# Motor-Z.net
KiCad netlist of a schematic drawn in Altium Designer
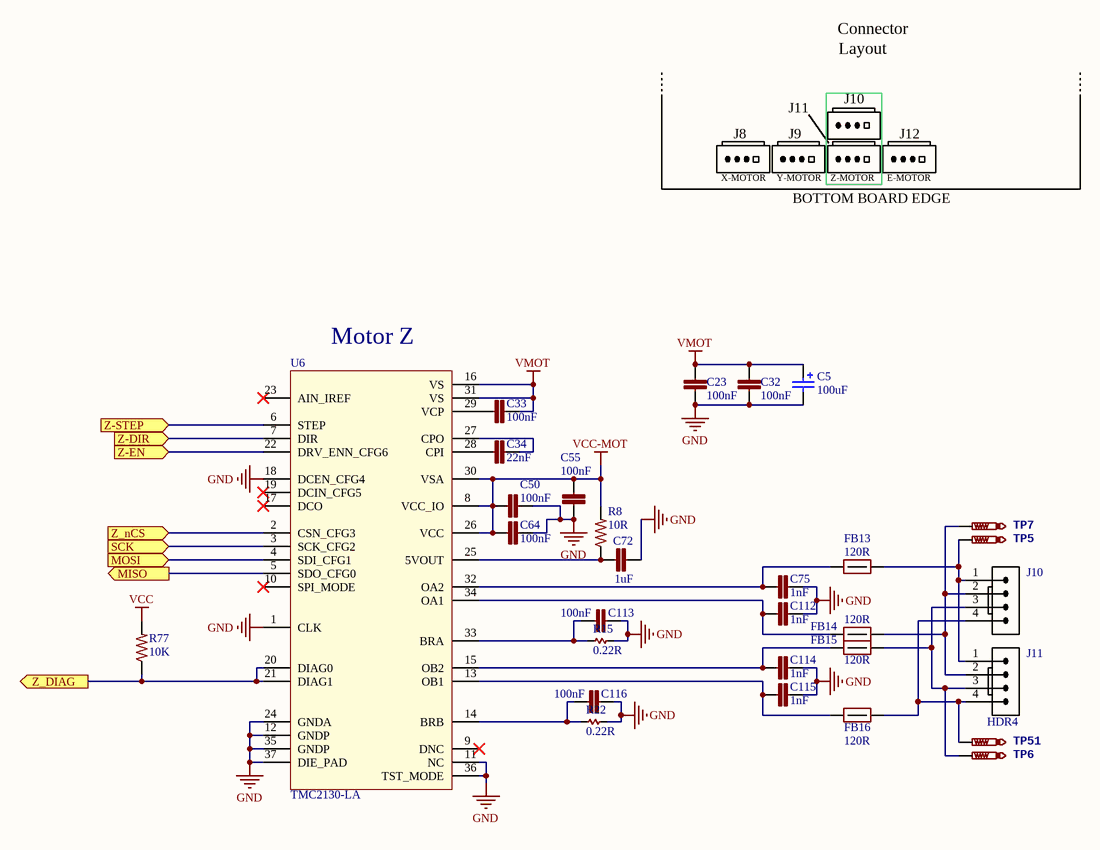
[diagram p0: Motor-Z.SchDoc]

(export (version "E")
  (design (tool "Eeschema 10.0.6"))
  (components
    (comp (ref "C5")
      (value "100uF")
      (footprint "CAP-ELEC-063063077")
      (description "CAP ALUM 100UF 35V 20% SMD")
      (fields (field (name "MANUFACTURER") "Nichicon") (field (name "TOLERANCE") "+/- 20%"))
      (libsource (lib "3Delight") (part "UWT1V101MCL1GS"))
    )
    (comp (ref "C23")
      (value "100nF")
      (footprint "C0603")
      (description "CAP CER 0603 100nF 50V 10% X7R")
      (fields (field (name "MANUFACTURER") "Kemet") (field (name "TOLERANCE") "+/- 10%"))
      (libsource (lib "3Delight") (part "C0603C104K5RACTU"))
    )
    (comp (ref "C32")
      (value "100nF")
      (footprint "C0603")
      (description "CAP CER 0603 100nF 50V 10% X7R")
      (fields (field (name "MANUFACTURER") "Kemet") (field (name "TOLERANCE") "+/- 10%"))
      (libsource (lib "3Delight") (part "C0603C104K5RACTU"))
    )
    (comp (ref "C33")
      (value "100nF")
      (footprint "C0603")
      (description "CAP CER 0603 100nF 50V 10% X7R")
      (fields (field (name "MANUFACTURER") "Kemet") (field (name "TOLERANCE") "+/- 10%"))
      (libsource (lib "") (part "C0603C104K5RACTU_2"))
    )
    (comp (ref "C34")
      (value "22nF")
      (footprint "C0402")
      (description "CAP CER 0402 22nF ±10% 50V X7R")
      (fields (field (name "MANUFACTURER") "YAGEO") (field (name "TOLERANCE") "+/- 10%"))
      (libsource (lib "3Delight") (part "GCM155R71H223KA55D"))
    )
    (comp (ref "C50")
      (value "100nF")
      (footprint "C0402")
      (description "CAP CER 0402 100nF 16V 10% X7R")
      (fields (field (name "MANUFACTURER") "Murata") (field (name "TOLERANCE") "+/- 10%"))
      (libsource (lib "") (part "GRM155R71C104KA88D_1"))
    )
    (comp (ref "C55")
      (value "100nF")
      (footprint "C0402")
      (description "CAP CER 0402 100nF 16V 10% X7R")
      (fields (field (name "MANUFACTURER") "Murata") (field (name "TOLERANCE") "+/- 10%"))
      (libsource (lib "3Delight") (part "GRM155R71C104KA88D"))
    )
    (comp (ref "C64")
      (value "100nF")
      (footprint "C0402")
      (description "CAP CER 0402 100nF 16V 10% X7R")
      (fields (field (name "MANUFACTURER") "Murata") (field (name "TOLERANCE") "+/- 10%"))
      (libsource (lib "") (part "GRM155R71C104KA88D_1"))
    )
    (comp (ref "C72")
      (value "1uF")
      (footprint "C0402")
      (description "CAP CER 0402 1uF 6.3V 10% X5R")
      (fields (field (name "MANUFACTURER") "Murata") (field (name "TOLERANCE") "+/- 10%"))
      (libsource (lib "3Delight") (part "GRM155R60J105KE19D"))
    )
    (comp (ref "C75")
      (value "1nF")
      (footprint "C0603")
      (description "CAP CER 0603  1nF 50v 10% X7R")
      (fields (field (name "MANUFACTURER") "Kemet") (field (name "TOLERANCE") "+/- 10%"))
      (libsource (lib "3Delight") (part "C0603C102K5RACTU"))
    )
    (comp (ref "C112")
      (value "1nF")
      (footprint "C0603")
      (description "CAP CER 0603  1nF 50v 10% X7R")
      (fields (field (name "MANUFACTURER") "Kemet") (field (name "TOLERANCE") "+/- 10%"))
      (libsource (lib "3Delight") (part "C0603C102K5RACTU"))
    )
    (comp (ref "C113")
      (value "100nF")
      (footprint "C0603")
      (description "CAP CER 0603 100nF 50V 10% X7R")
      (fields (field (name "MANUFACTURER") "Kemet") (field (name "TOLERANCE") "+/- 10%"))
      (libsource (lib "") (part "C0603C104K5RACTU_1"))
    )
    (comp (ref "C114")
      (value "1nF")
      (footprint "C0603")
      (description "CAP CER 0603  1nF 50v 10% X7R")
      (fields (field (name "MANUFACTURER") "Kemet") (field (name "TOLERANCE") "+/- 10%"))
      (libsource (lib "3Delight") (part "C0603C102K5RACTU"))
    )
    (comp (ref "C115")
      (value "1nF")
      (footprint "C0603")
      (description "CAP CER 0603  1nF 50v 10% X7R")
      (fields (field (name "MANUFACTURER") "Kemet") (field (name "TOLERANCE") "+/- 10%"))
      (libsource (lib "3Delight") (part "C0603C102K5RACTU"))
    )
    (comp (ref "C116")
      (value "100nF")
      (footprint "C0603")
      (description "CAP CER 0603 100nF 50V 10% X7R")
      (fields (field (name "MANUFACTURER") "Kemet") (field (name "TOLERANCE") "+/- 10%"))
      (libsource (lib "") (part "C0603C104K5RACTU_1"))
    )
    (comp (ref "FB13")
      (value "120R")
      (footprint "FB0603")
      (description "FERRITE BEAD 120 OHM 0603 1LN")
      (fields (field (name "MANUFACTURER") "Samsung") (field (name "PART") "FERRITE 120R 3A 0603"))
      (libsource (lib "Inductors") (part "FERRITE 120R 3A 0603"))
    )
    (comp (ref "FB14")
      (value "120R")
      (footprint "FB0603")
      (description "FERRITE BEAD 120 OHM 0603 1LN")
      (fields (field (name "MANUFACTURER") "Samsung") (field (name "PART") "FERRITE 120R 3A 0603"))
      (libsource (lib "Inductors") (part "FERRITE 120R 3A 0603"))
    )
    (comp (ref "FB15")
      (value "120R")
      (footprint "FB0603")
      (description "FERRITE BEAD 120 OHM 0603 1LN")
      (fields (field (name "MANUFACTURER") "Samsung") (field (name "PART") "FERRITE 120R 3A 0603"))
      (libsource (lib "Inductors") (part "FERRITE 120R 3A 0603"))
    )
    (comp (ref "FB16")
      (value "120R")
      (footprint "FB0603")
      (description "FERRITE BEAD 120 OHM 0603 1LN")
      (fields (field (name "MANUFACTURER") "Samsung") (field (name "PART") "FERRITE 120R 3A 0603"))
      (libsource (lib "Inductors") (part "FERRITE 120R 3A 0603"))
    )
    (comp (ref "J10")
      (value "Molex 0705430003")
      (footprint "4POL254")
      (description "Molex 4 Pin Clip Connector")
      (fields (field (name "MANUFACTURER") "Molex") (field (name "PART") "4 Pin Conn"))
      (libsource (lib "3Delight") (part "CONN 4PIN 0.1{dblquote} VERT SHRD LOCK ALT"))
    )
    (comp (ref "J11")
      (value "HDR4")
      (footprint "4POL254")
      (description "Molex 4 Pin Clip Connector")
      (fields (field (name "MANUFACTURER") "Molex") (field (name "PART") "4 Pin Conn"))
      (libsource (lib "3Delight") (part "CONN 4PIN 0.1{dblquote} VERT SHRD LOCK ALT"))
    )
    (comp (ref "R8")
      (value "10R")
      (footprint "R0402")
      (description "RES SMD 10 OHM 1% 1/16W 0402")
      (fields (field (name "MANUFACTURER") "Yageo") (field (name "TOLERANCE") "+/- 1%"))
      (libsource (lib "3Delight") (part "RC0402FR-0710RL"))
    )
    (comp (ref "R15")
      (value "0.22R")
      (footprint "R1206")
      (description "RES SMD 0.22 OHM 1% 1/3W 1206")
      (fields (field (name "MANUFACTURER") "Panasonic") (field (name "TOLERANCE") "+/- 1%"))
      (libsource (lib "Resistors") (part "0.22R 1% 1206"))
    )
    (comp (ref "R22")
      (value "0.22R")
      (footprint "R1206")
      (description "RES SMD 0.22 OHM 1% 1/3W 1206")
      (fields (field (name "MANUFACTURER") "Panasonic") (field (name "TOLERANCE") "+/- 1%"))
      (libsource (lib "Resistors") (part "0.22R 1% 1206"))
    )
    (comp (ref "R77")
      (value "10K")
      (footprint "R0402")
      (description "RES SMD 10K OHM 1% 1/16W 0402")
      (fields (field (name "MANUFACTURER") "Yageo") (field (name "PART") "10k 1% 0402"))
      (libsource (lib "3Delight") (part "RC0402FR-0710KP"))
    )
    (comp (ref "TP5")
      (value "TestPoint")
      (footprint "TP1-27")
      (description "Test Point")
      (libsource (lib "3Delight") (part "TestPoint"))
    )
    (comp (ref "TP6")
      (value "TestPoint")
      (footprint "TP1-27")
      (description "Test Point")
      (libsource (lib "3Delight") (part "TestPoint"))
    )
    (comp (ref "TP7")
      (value "TestPoint")
      (footprint "TP1-27")
      (description "Test Point")
      (libsource (lib "3Delight") (part "TestPoint"))
    )
    (comp (ref "TP51")
      (value "TestPoint")
      (footprint "TP1-27")
      (description "Test Point")
      (libsource (lib "3Delight") (part "TestPoint"))
    )
    (comp (ref "U6")
      (value "TMC2130-LA")
      (footprint "QFN36-50P500X600X900_HS-37N")
      (description "IC STEPPER MOTOR DVR SPI 36QFN")
      (fields (field (name "MANUFACTURER") "Trinamic") (field (name "PART") "TMC2130"))
      (libsource (lib "3Delight") (part "TMC2130-LA-T"))
    )
  )
  (nets
    (net (code "1") (name "/MISO") (class "Default")
      (node (ref "U6") (pin "5") (pinfunction "SDO_CFG0_5") (pintype "passive"))
    )
    (net (code "2") (name "/MOSI") (class "Default")
      (node (ref "U6") (pin "4") (pinfunction "SDI_CFG1_4") (pintype "passive"))
    )
    (net (code "3") (name "/SCK") (class "Default")
      (node (ref "U6") (pin "3") (pinfunction "SCK_CFG2_3") (pintype "passive"))
    )
    (net (code "4") (name "/Z-DIR") (class "Default")
      (node (ref "U6") (pin "7") (pinfunction "DIR_7") (pintype "passive"))
    )
    (net (code "5") (name "/Z-EN") (class "Default")
      (node (ref "U6") (pin "22") (pinfunction "DRV_ENN_CFG6_22") (pintype "passive"))
    )
    (net (code "6") (name "/Z-STEP") (class "Default")
      (node (ref "U6") (pin "6") (pinfunction "STEP_6") (pintype "passive"))
    )
    (net (code "7") (name "/Z_DIAG") (class "Default")
      (node (ref "R77") (pin "1") (pinfunction "1_1") (pintype "passive"))
      (node (ref "U6") (pin "20") (pinfunction "DIAG0_20") (pintype "passive"))
      (node (ref "U6") (pin "21") (pinfunction "DIAG1_21") (pintype "passive"))
    )
    (net (code "8") (name "/Z_nCS") (class "Default")
      (node (ref "U6") (pin "2") (pinfunction "CSN_CFG3_2") (pintype "passive"))
    )
    (net (code "9") (name "GND") (class "Default")
      (node (ref "C112") (pin "2") (pinfunction "2_2") (pintype "passive"))
      (node (ref "C113") (pin "1") (pinfunction "1_1") (pintype "passive"))
      (node (ref "C114") (pin "2") (pinfunction "2_2") (pintype "passive"))
      (node (ref "C115") (pin "2") (pinfunction "2_2") (pintype "passive"))
      (node (ref "C116") (pin "1") (pinfunction "1_1") (pintype "passive"))
      (node (ref "C23") (pin "1") (pinfunction "1_1") (pintype "passive"))
      (node (ref "C32") (pin "1") (pinfunction "1_1") (pintype "passive"))
      (node (ref "C5") (pin "2") (pinfunction "2_2") (pintype "passive"))
      (node (ref "C50") (pin "1") (pinfunction "1_1") (pintype "passive"))
      (node (ref "C55") (pin "1") (pinfunction "1_1") (pintype "passive"))
      (node (ref "C64") (pin "1") (pinfunction "1_1") (pintype "passive"))
      (node (ref "C72") (pin "2") (pinfunction "2_2") (pintype "passive"))
      (node (ref "C75") (pin "2") (pinfunction "2_2") (pintype "passive"))
      (node (ref "R15") (pin "2") (pinfunction "2_2") (pintype "passive"))
      (node (ref "R22") (pin "2") (pinfunction "2_2") (pintype "passive"))
      (node (ref "U6") (pin "1") (pinfunction "CLK_1") (pintype "passive"))
      (node (ref "U6") (pin "11") (pinfunction "NC_11") (pintype "passive"))
      (node (ref "U6") (pin "12") (pinfunction "GNDP_12") (pintype "passive"))
      (node (ref "U6") (pin "18") (pinfunction "DCEN_CFG4_18") (pintype "passive"))
      (node (ref "U6") (pin "24") (pinfunction "GNDA_24") (pintype "passive"))
      (node (ref "U6") (pin "35") (pinfunction "GNDP_35") (pintype "passive"))
      (node (ref "U6") (pin "36") (pinfunction "TST_MODE_36") (pintype "passive"))
      (node (ref "U6") (pin "37") (pinfunction "DIE_PAD_37") (pintype "passive"))
    )
    (net (code "10") (name "Net-(FB13-Pad2)") (class "Default")
      (node (ref "FB13") (pin "2") (pinfunction "2_2") (pintype "passive"))
      (node (ref "J10") (pin "1") (pinfunction "1_1") (pintype "passive"))
      (node (ref "J11") (pin "1") (pinfunction "1_1") (pintype "passive"))
      (node (ref "TP5") (pin "TP") (pinfunction "TP_TP") (pintype "passive"))
    )
    (net (code "11") (name "Net-(FB14-Pad2)") (class "Default")
      (node (ref "FB14") (pin "2") (pinfunction "2_2") (pintype "passive"))
      (node (ref "J10") (pin "2") (pinfunction "2_2") (pintype "passive"))
      (node (ref "J11") (pin "2") (pinfunction "2_2") (pintype "passive"))
      (node (ref "TP7") (pin "TP") (pinfunction "TP_TP") (pintype "passive"))
    )
    (net (code "12") (name "Net-(FB15-Pad2)") (class "Default")
      (node (ref "FB15") (pin "2") (pinfunction "2_2") (pintype "passive"))
      (node (ref "J10") (pin "3") (pinfunction "3_3") (pintype "passive"))
      (node (ref "J11") (pin "3") (pinfunction "3_3") (pintype "passive"))
      (node (ref "TP6") (pin "TP") (pinfunction "TP_TP") (pintype "passive"))
    )
    (net (code "13") (name "Net-(FB16-Pad2)") (class "Default")
      (node (ref "FB16") (pin "2") (pinfunction "2_2") (pintype "passive"))
      (node (ref "J10") (pin "4") (pinfunction "4_4") (pintype "passive"))
      (node (ref "J11") (pin "4") (pinfunction "4_4") (pintype "passive"))
      (node (ref "TP51") (pin "TP") (pinfunction "TP_TP") (pintype "passive"))
    )
    (net (code "14") (name "Net-(U6-5VOUT)") (class "Default")
      (node (ref "C72") (pin "1") (pinfunction "1_1") (pintype "passive"))
      (node (ref "R8") (pin "1") (pinfunction "1_1") (pintype "passive"))
      (node (ref "U6") (pin "25") (pinfunction "5VOUT_25") (pintype "passive"))
    )
    (net (code "15") (name "Net-(U6-BRA)") (class "Default")
      (node (ref "C113") (pin "2") (pinfunction "2_2") (pintype "passive"))
      (node (ref "R15") (pin "1") (pinfunction "1_1") (pintype "passive"))
      (node (ref "U6") (pin "33") (pinfunction "BRA_33") (pintype "passive"))
    )
    (net (code "16") (name "Net-(U6-BRB)") (class "Default")
      (node (ref "C116") (pin "2") (pinfunction "2_2") (pintype "passive"))
      (node (ref "R22") (pin "1") (pinfunction "1_1") (pintype "passive"))
      (node (ref "U6") (pin "14") (pinfunction "BRB_14") (pintype "passive"))
    )
    (net (code "17") (name "Net-(U6-CPI)") (class "Default")
      (node (ref "C34") (pin "1") (pinfunction "1_1") (pintype "passive"))
      (node (ref "U6") (pin "28") (pinfunction "CPI_28") (pintype "passive"))
    )
    (net (code "18") (name "Net-(U6-CPO)") (class "Default")
      (node (ref "C34") (pin "2") (pinfunction "2_2") (pintype "passive"))
      (node (ref "U6") (pin "27") (pinfunction "CPO_27") (pintype "passive"))
    )
    (net (code "19") (name "Net-(U6-OA1)") (class "Default")
      (node (ref "C112") (pin "1") (pinfunction "1_1") (pintype "passive"))
      (node (ref "FB14") (pin "1") (pinfunction "1_1") (pintype "passive"))
      (node (ref "U6") (pin "34") (pinfunction "OA1_34") (pintype "passive"))
    )
    (net (code "20") (name "Net-(U6-OA2)") (class "Default")
      (node (ref "C75") (pin "1") (pinfunction "1_1") (pintype "passive"))
      (node (ref "FB13") (pin "1") (pinfunction "1_1") (pintype "passive"))
      (node (ref "U6") (pin "32") (pinfunction "OA2_32") (pintype "passive"))
    )
    (net (code "21") (name "Net-(U6-OB1)") (class "Default")
      (node (ref "C115") (pin "1") (pinfunction "1_1") (pintype "passive"))
      (node (ref "FB16") (pin "1") (pinfunction "1_1") (pintype "passive"))
      (node (ref "U6") (pin "13") (pinfunction "OB1_13") (pintype "passive"))
    )
    (net (code "22") (name "Net-(U6-OB2)") (class "Default")
      (node (ref "C114") (pin "1") (pinfunction "1_1") (pintype "passive"))
      (node (ref "FB15") (pin "1") (pinfunction "1_1") (pintype "passive"))
      (node (ref "U6") (pin "15") (pinfunction "OB2_15") (pintype "passive"))
    )
    (net (code "23") (name "Net-(U6-VCP)") (class "Default")
      (node (ref "C33") (pin "1") (pinfunction "1_1") (pintype "passive"))
      (node (ref "U6") (pin "29") (pinfunction "VCP_29") (pintype "passive"))
    )
    (net (code "24") (name "VCC") (class "Default")
      (node (ref "R77") (pin "2") (pinfunction "2_2") (pintype "passive"))
    )
    (net (code "25") (name "VCC-MOT") (class "Default")
      (node (ref "C50") (pin "2") (pinfunction "2_2") (pintype "passive"))
      (node (ref "C55") (pin "2") (pinfunction "2_2") (pintype "passive"))
      (node (ref "C64") (pin "2") (pinfunction "2_2") (pintype "passive"))
      (node (ref "R8") (pin "2") (pinfunction "2_2") (pintype "passive"))
      (node (ref "U6") (pin "26") (pinfunction "VCC_26") (pintype "passive"))
      (node (ref "U6") (pin "30") (pinfunction "VSA_30") (pintype "passive"))
      (node (ref "U6") (pin "8") (pinfunction "VCC_IO_8") (pintype "passive"))
    )
    (net (code "26") (name "VMOT") (class "Default")
      (node (ref "C23") (pin "2") (pinfunction "2_2") (pintype "passive"))
      (node (ref "C32") (pin "2") (pinfunction "2_2") (pintype "passive"))
      (node (ref "C33") (pin "2") (pinfunction "2_2") (pintype "passive"))
      (node (ref "C5") (pin "1") (pinfunction "1_1") (pintype "passive"))
      (node (ref "U6") (pin "16") (pinfunction "VS_16") (pintype "passive"))
      (node (ref "U6") (pin "31") (pinfunction "VS_31") (pintype "passive"))
    )
    (net (code "27") (name "unconnected-(U6-AIN_IREF-Pad23)") (class "Default")
      (node (ref "U6") (pin "23") (pinfunction "AIN_IREF_23") (pintype "passive+no_connect"))
    )
    (net (code "28") (name "unconnected-(U6-DCIN_CFG5-Pad19)") (class "Default")
      (node (ref "U6") (pin "19") (pinfunction "DCIN_CFG5_19") (pintype "passive+no_connect"))
    )
    (net (code "29") (name "unconnected-(U6-DCO-Pad17)") (class "Default")
      (node (ref "U6") (pin "17") (pinfunction "DCO_17") (pintype "passive+no_connect"))
    )
    (net (code "30") (name "unconnected-(U6-DNC-Pad9)") (class "Default")
      (node (ref "U6") (pin "9") (pinfunction "DNC_9") (pintype "passive+no_connect"))
    )
    (net (code "31") (name "unconnected-(U6-SPI_MODE-Pad10)") (class "Default")
      (node (ref "U6") (pin "10") (pinfunction "SPI_MODE_10") (pintype "passive+no_connect"))
    )
  )
)
